# CSI2-WAND_Rev01.net
KiCad netlist of a schematic drawn in Altium Designer
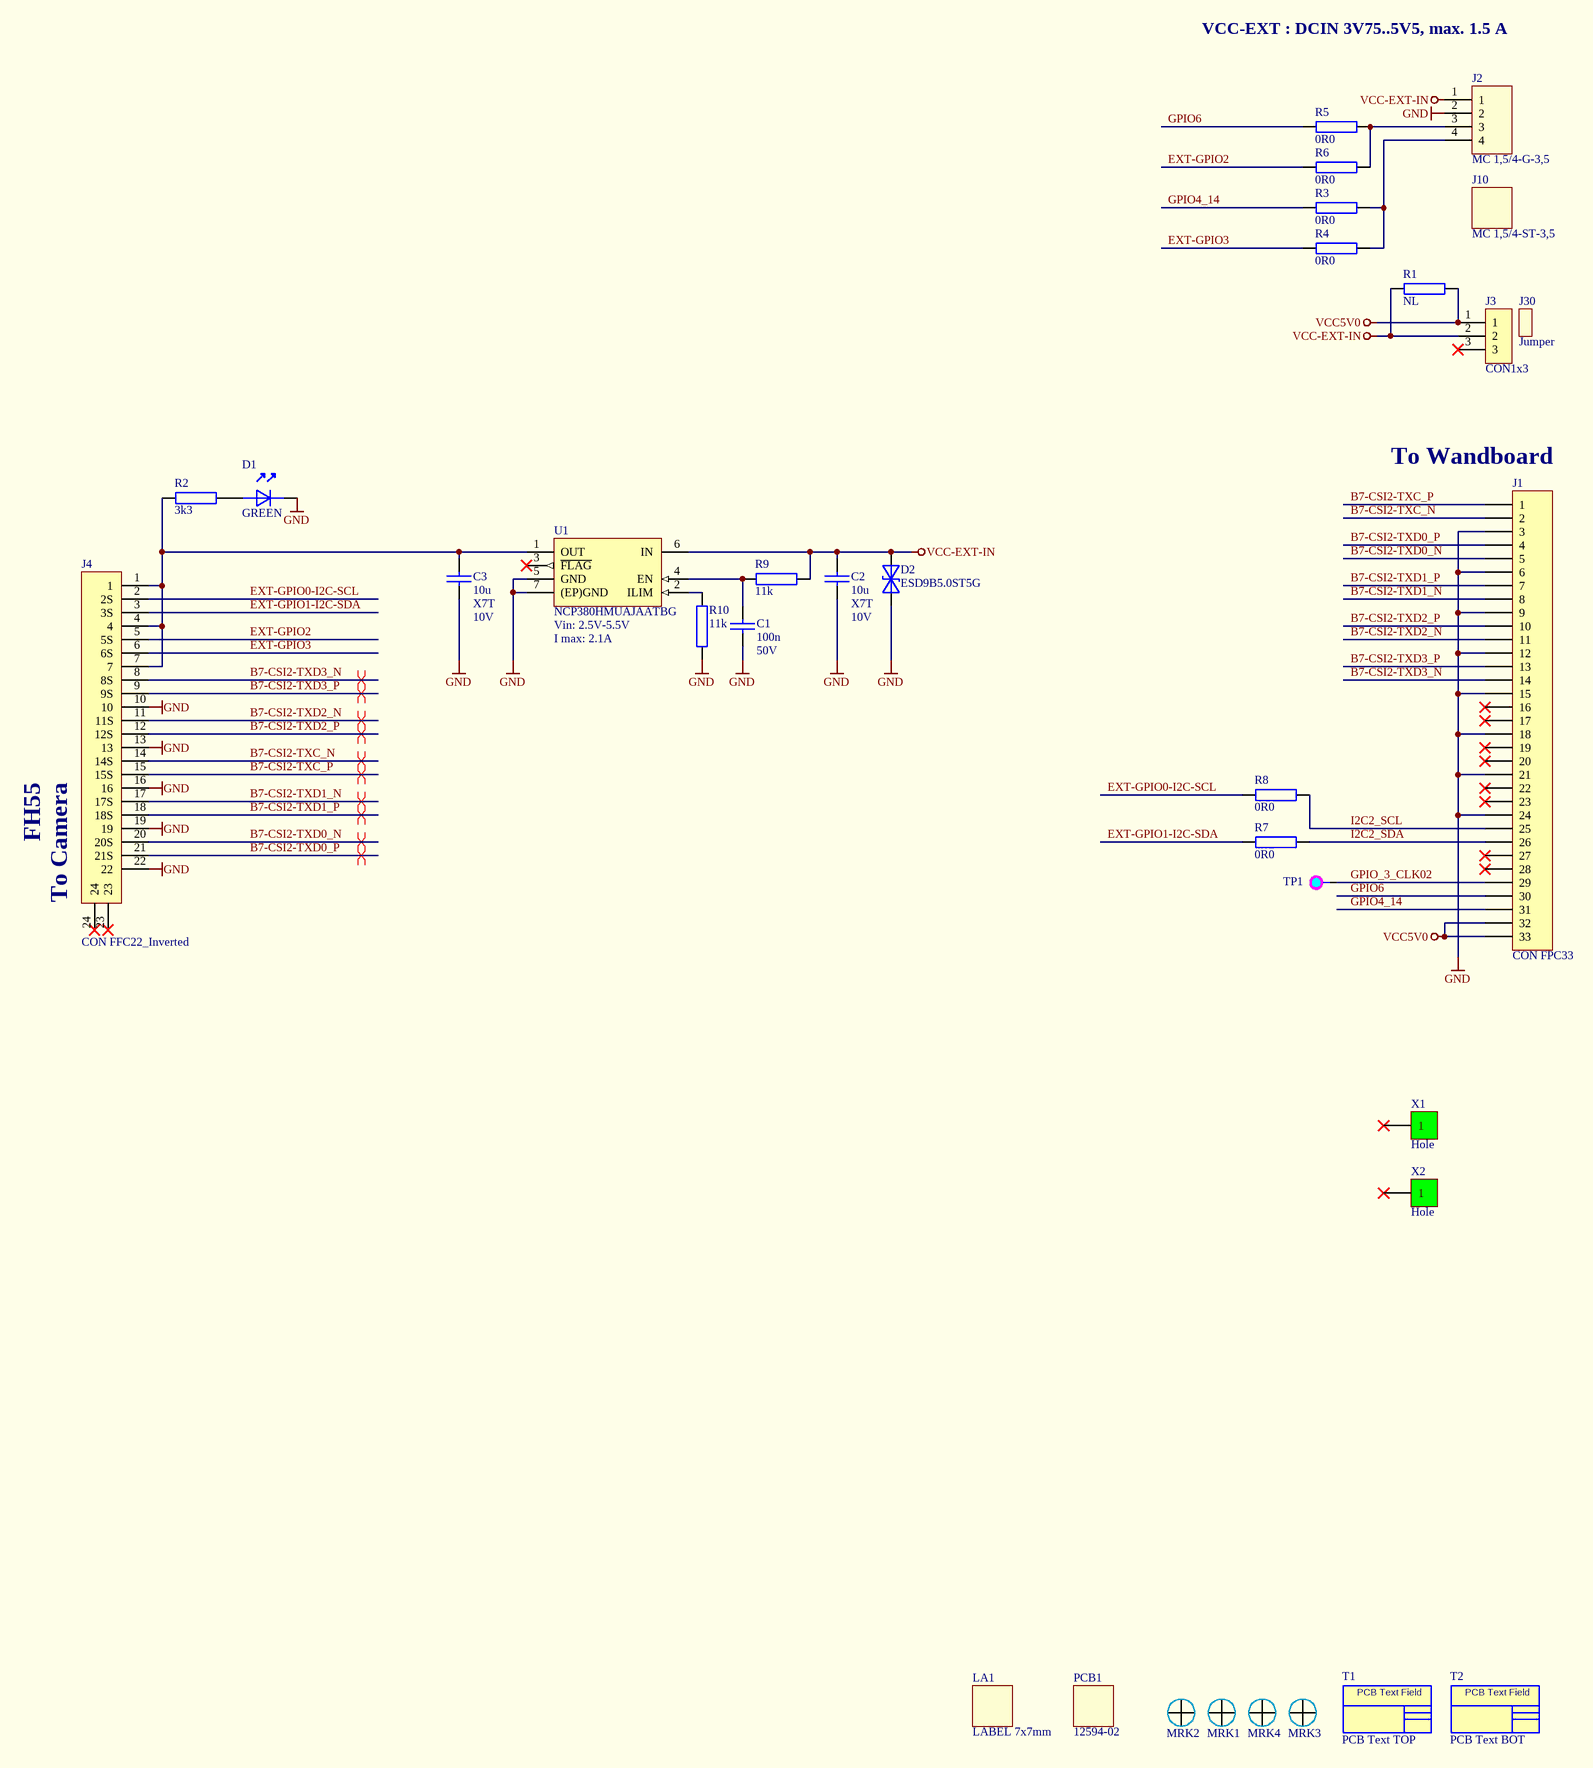
[diagram p0: CSI2-WAND_Rev01.SchDoc]

(export (version "E")
  (design (tool "Eeschema 10.0.6"))
  (components
    (comp (ref "C1")
      (value "100n")
      (footprint "C-0603_1.0")
      (description "Capacitor Ceramic SMD/0603/50V/X7R/10%")
      (fields
        (field (name "KHK PART NUMBER") "K8340023")
        (field (name "MANUFACTURER") "several")
        (field (name "VOLTAGE") "50V")
      )
      (libsource (lib "AVT_KHK_Lib") (part "C 100N 50V X7R 0603"))
    )
    (comp (ref "C2")
      (value "10u")
      (footprint "C-0603_1.0")
      (description "Capacitor Ceramic SMD/0603/10V/X7T/20%/125°C")
      (fields
        (field (name "KHK PART NUMBER") "10509")
        (field (name "MANUFACTURER") "several")
        (field (name "DIELECTRIC") "X7T")
        (field (name "VOLTAGE") "10V")
      )
      (libsource (lib "AVT_KHK_Lib") (part "C 10U 10V X7T 0603 125°C"))
    )
    (comp (ref "C3")
      (value "10u")
      (footprint "C-0603_1.0")
      (description "Capacitor Ceramic SMD/0603/10V/X7T/20%/125°C")
      (fields
        (field (name "KHK PART NUMBER") "10509")
        (field (name "MANUFACTURER") "several")
        (field (name "DIELECTRIC") "X7T")
        (field (name "VOLTAGE") "10V")
      )
      (libsource (lib "AVT_KHK_Lib") (part "C 10U 10V X7T 0603 125°C"))
    )
    (comp (ref "D1")
      (value "GREEN")
      (footprint "D-0603-LED")
      (description "Chip LED green 430mcd")
      (fields (field (name "KHK PART NUMBER") "8172") (field (name "MANUFACTURER") "Würth"))
      (libsource (lib "AVT_KHK_Lib") (part "D LED 0603 green"))
    )
    (comp (ref "D2")
      (value "ESD9B5.0ST5G")
      (footprint "D-SOD923")
      (description "DIODE TVS; 400W; 5.8-7.8V; BIDIRECT")
      (fields (field (name "KHK PART NUMBER") "7250") (field (name "MANUFACTURER") "ON Semiconductor"))
      (libsource (lib "AVT_KHK_Lib") (part "D ESD9B5.0ST5G"))
    )
    (comp (ref "J1")
      (value "CON FPC33")
      (footprint "CON33_FLEX_FPC3.5_5- Inverted Pins")
      (description "FPC Connector 0.5mm FLEX PCB")
      (libsource (lib "AVT_KHK_Lib") (part "CON FPC33_FLEXPCB"))
    )
    (comp (ref "J2")
      (value "MC 1,5/4-G-3,5")
      (footprint "CON_MiniCon 4pol 3mm5")
      (description "Phoenix MC 1,5/4-G-3,5 MiniCon 4polig 3,5mm")
      (fields (field (name "KHK PART NUMBER") "12637") (field (name "MANUFACTURER") "Phoenix"))
      (libsource (lib "AVT_KHK_Lib") (part "CON MiniCon 4pol 3mm5"))
    )
    (comp (ref "J3")
      (value "CON1x3")
      (footprint "CON 1x3 RM2.54")
      (description "Stiftleiste; 1x3; 2.54mm; gerade")
      (fields
        (field (name "MANUFACTURER") "fischer elektronik")
        (field (name "MANUFACTURER PART NUMBER") "SL 11 124 3 G")
      )
      (libsource (lib "AVT_KHK_Lib") (part "CON 1x3 2.54"))
    )
    (comp (ref "J4")
      (value "CON FFC22_Inverted")
      (footprint "J-FH55-22S-0.5SH - Inverted Pins")
      (description "FFC Connector 0.5mm shielded")
      (fields
        (field (name "KHK PART NUMBER") "10357")
        (field (name "MANUFACTURER PART NUMBER") "FH55-22S-0.5SH")
      )
      (libsource (lib "AVT_KHK_Lib") (part "CON FFC22_FH55-22S-0.5SH_Inverted"))
    )
    (comp (ref "J10")
      (value "MC 1,5/4-ST-3,5")
      (description "Phoenix MC 1,5/4-ST-3,5 MiniCon 4polig 3,5mm")
      (fields (field (name "KHK PART NUMBER") "12635") (field (name "MANUFACTURER") "Phoenix"))
      (libsource (lib "AVT_KHK_Lib") (part "CON MiniCon 4pol 3mm5 ST"))
    )
    (comp (ref "J30")
      (value "Jumper")
      (footprint "J-JUMPER-2.54")
      (description "CON/JUMPER/STC02SYAN; 2-pin; 2.54mm; 3A; FEMALE; VERTICAL; BLACK")
      (fields (field (name "KHK PART NUMBER") "13444") (field (name "MANUFACTURER") "several"))
      (libsource (lib "AVT_KHK_Lib") (part "CON Jumper 2.54mm"))
    )
    (comp (ref "LA1")
      (value "LABEL 7x7mm")
      (footprint "PCB LABEL 7x7")
      (fields (field (name "MANUFACTURER") "several"))
      (libsource (lib "AVT_KHK_Lib") (part "PCB LABEL 7x7"))
    )
    (comp (ref "MRK1")
      (value "Marker Single Layer")
      (footprint "PCB_Marker_Pad_top")
      (description "Position Marker for PCBs")
      (libsource (lib "AVT_KHK_Lib") (part "PCB Marker Pad Single Layer"))
    )
    (comp (ref "MRK2")
      (value "Marker Single Layer")
      (footprint "PCB_Marker_Pad_top")
      (description "Position Marker for PCBs")
      (libsource (lib "AVT_KHK_Lib") (part "PCB Marker Pad Single Layer"))
    )
    (comp (ref "MRK3")
      (value "Marker Single Layer")
      (footprint "PCB_Marker_Pad_top")
      (description "Position Marker for PCBs")
      (libsource (lib "AVT_KHK_Lib") (part "PCB Marker Pad Single Layer"))
    )
    (comp (ref "MRK4")
      (value "Marker Single Layer")
      (footprint "PCB_Marker_Pad_top")
      (description "Position Marker for PCBs")
      (libsource (lib "AVT_KHK_Lib") (part "PCB Marker Pad Single Layer"))
    )
    (comp (ref "PCB1")
      (value "12594-02")
      (description "PCB ML04")
      (fields (field (name "MANUFACTURER") "several"))
      (libsource (lib "AVT_KHK_Lib") (part "PCB"))
    )
    (comp (ref "R1")
      (value "NL")
      (footprint "R-0603_0.6")
      (description "Standard Resistor SMD/0603/1%/100mW/TK100")
      (fields (field (name "TOLERANCE") "1%"))
      (libsource (lib "AVT_KHK_Lib") (part "R X 0603"))
    )
    (comp (ref "R2")
      (value "3k3")
      (footprint "R-0603_0.6")
      (description "Standard Resistor SMD/0603/1%/100mW/TK100")
      (fields (field (name "KHK PART NUMBER") "K8250070") (field (name "MANUFACTURER") "several"))
      (libsource (lib "AVT_KHK_Lib") (part "R 3K3 1% 0603"))
    )
    (comp (ref "R3")
      (value "0R0")
      (footprint "R-0603_0.6")
      (description "Standard Resistor SMD/0603/1%/100mW/TK100")
      (fields (field (name "KHK PART NUMBER") "K8250041") (field (name "MANUFACTURER") "several"))
      (libsource (lib "AVT_KHK_Lib") (part "R 0R0 1% 0603"))
    )
    (comp (ref "R4")
      (value "0R0")
      (footprint "R-0603_0.6")
      (description "Standard Resistor SMD/0603/1%/100mW/TK100")
      (fields (field (name "KHK PART NUMBER") "K8250041") (field (name "MANUFACTURER") "several"))
      (libsource (lib "AVT_KHK_Lib") (part "R 0R0 1% 0603"))
    )
    (comp (ref "R5")
      (value "0R0")
      (footprint "R-0603_0.6")
      (description "Standard Resistor SMD/0603/1%/100mW/TK100")
      (fields (field (name "KHK PART NUMBER") "K8250041") (field (name "MANUFACTURER") "several"))
      (libsource (lib "AVT_KHK_Lib") (part "R 0R0 1% 0603"))
    )
    (comp (ref "R6")
      (value "0R0")
      (footprint "R-0603_0.6")
      (description "Standard Resistor SMD/0603/1%/100mW/TK100")
      (fields (field (name "KHK PART NUMBER") "K8250041") (field (name "MANUFACTURER") "several"))
      (libsource (lib "AVT_KHK_Lib") (part "R 0R0 1% 0603"))
    )
    (comp (ref "R7")
      (value "0R0")
      (footprint "R-0603_0.6")
      (description "Standard Resistor SMD/0603/1%/100mW/TK100")
      (fields (field (name "KHK PART NUMBER") "K8250041") (field (name "MANUFACTURER") "several"))
      (libsource (lib "AVT_KHK_Lib") (part "R 0R0 1% 0603"))
    )
    (comp (ref "R8")
      (value "0R0")
      (footprint "R-0603_0.6")
      (description "Standard Resistor SMD/0603/1%/100mW/TK100")
      (fields (field (name "KHK PART NUMBER") "K8250041") (field (name "MANUFACTURER") "several"))
      (libsource (lib "AVT_KHK_Lib") (part "R 0R0 1% 0603"))
    )
    (comp (ref "R9")
      (value "11k")
      (footprint "R-0603_0.6")
      (description "Standard Resistor SMD/0603/1%/100mW/TK100")
      (fields (field (name "KHK PART NUMBER") "K8250147") (field (name "MANUFACTURER") "several"))
      (libsource (lib "AVT_KHK_Lib") (part "R 11K 1% 0603"))
    )
    (comp (ref "R10")
      (value "11k")
      (footprint "R-0603_0.6")
      (description "Standard Resistor SMD/0603/1%/100mW/TK100")
      (fields (field (name "KHK PART NUMBER") "K8250147") (field (name "MANUFACTURER") "several"))
      (libsource (lib "AVT_KHK_Lib") (part "R 11K 1% 0603"))
    )
    (comp (ref "T1")
      (value "PCB Text TOP")
      (footprint "PCB TEXTFIELD TOP 2")
      (description "PCB Textfield TOP")
      (libsource (lib "AVT_KHK_Lib") (part "PCB TEXT FIELD TOP"))
    )
    (comp (ref "T2")
      (value "PCB Text BOT")
      (footprint "PCB TEXTFIELD BOT 2")
      (description "PCB Textfield BOT")
      (libsource (lib "AVT_KHK_Lib") (part "PCB TEXT FIELD BOT"))
    )
    (comp (ref "TP1")
      (value "TP")
      (footprint "TP_11_065")
      (description "Testpoint: Pad=1,1mm; Hole=0,65mm")
      (libsource (lib "AVT_KHK_Lib") (part "TP_11_065"))
    )
    (comp (ref "U1")
      (value "NCP380HMUAJAATBG")
      (footprint "IC-DFN06_2.0x2.0x0.8")
      (description "IC/PWR/LOADSW;1V2-5V5;3A;0R03/WLCSP6/1x1.5x0.63mm")
      (fields
        (field (name "KHK PART NUMBER") "13676")
        (field (name "MANUFACTURER") "onsemi")
        (field (name "VIN") "2.5V-5.5V")
        (field (name "I MAX") "2.1A")
      )
      (libsource (lib "AVT_KHK_Lib") (part "IC  NCP380HMUAJAATBG"))
    )
    (comp (ref "X1")
      (value "Hole")
      (footprint "HOLE-3.2-6.0-DK")
      (description "HOLE M3")
      (libsource (lib "AVT_KHK_Lib") (part "PCB HOLE M3-6-DK"))
    )
    (comp (ref "X2")
      (value "Hole")
      (footprint "HOLE-3.2-6.0-DK")
      (description "HOLE M3")
      (libsource (lib "AVT_KHK_Lib") (part "PCB HOLE M3-6-DK"))
    )
  )
  (nets
    (net (code "1") (name "/B7-CSI2-TXC_N") (class "Default")
      (node (ref "J1") (pin "2") (pinfunction "2_2") (pintype "passive"))
      (node (ref "J4") (pin "14") (pinfunction "14S_14") (pintype "passive"))
    )
    (net (code "2") (name "/B7-CSI2-TXC_P") (class "Default")
      (node (ref "J1") (pin "1") (pinfunction "1_1") (pintype "passive"))
      (node (ref "J4") (pin "15") (pinfunction "15S_15") (pintype "passive"))
    )
    (net (code "3") (name "/B7-CSI2-TXD0_N") (class "Default")
      (node (ref "J1") (pin "5") (pinfunction "5_5") (pintype "passive"))
      (node (ref "J4") (pin "20") (pinfunction "20S_20") (pintype "passive"))
    )
    (net (code "4") (name "/B7-CSI2-TXD0_P") (class "Default")
      (node (ref "J1") (pin "4") (pinfunction "4_4") (pintype "passive"))
      (node (ref "J4") (pin "21") (pinfunction "21S_21") (pintype "passive"))
    )
    (net (code "5") (name "/B7-CSI2-TXD1_N") (class "Default")
      (node (ref "J1") (pin "8") (pinfunction "8_8") (pintype "passive"))
      (node (ref "J4") (pin "17") (pinfunction "17S_17") (pintype "passive"))
    )
    (net (code "6") (name "/B7-CSI2-TXD1_P") (class "Default")
      (node (ref "J1") (pin "7") (pinfunction "7_7") (pintype "passive"))
      (node (ref "J4") (pin "18") (pinfunction "18S_18") (pintype "passive"))
    )
    (net (code "7") (name "/B7-CSI2-TXD2_N") (class "Default")
      (node (ref "J1") (pin "11") (pinfunction "11_11") (pintype "passive"))
      (node (ref "J4") (pin "11") (pinfunction "11S_11") (pintype "passive"))
    )
    (net (code "8") (name "/B7-CSI2-TXD2_P") (class "Default")
      (node (ref "J1") (pin "10") (pinfunction "10_10") (pintype "passive"))
      (node (ref "J4") (pin "12") (pinfunction "12S_12") (pintype "passive"))
    )
    (net (code "9") (name "/B7-CSI2-TXD3_N") (class "Default")
      (node (ref "J1") (pin "14") (pinfunction "14_14") (pintype "passive"))
      (node (ref "J4") (pin "8") (pinfunction "8S_8") (pintype "passive"))
    )
    (net (code "10") (name "/B7-CSI2-TXD3_P") (class "Default")
      (node (ref "J1") (pin "13") (pinfunction "13_13") (pintype "passive"))
      (node (ref "J4") (pin "9") (pinfunction "9S_9") (pintype "passive"))
    )
    (net (code "11") (name "/EXT-GPIO0-I2C-SCL") (class "Default")
      (node (ref "J4") (pin "2") (pinfunction "2S_2") (pintype "passive"))
      (node (ref "R8") (pin "2") (pinfunction "2_2") (pintype "passive"))
    )
    (net (code "12") (name "/EXT-GPIO1-I2C-SDA") (class "Default")
      (node (ref "J4") (pin "3") (pinfunction "3S_3") (pintype "passive"))
      (node (ref "R7") (pin "2") (pinfunction "2_2") (pintype "passive"))
    )
    (net (code "13") (name "/EXT-GPIO2") (class "Default")
      (node (ref "J4") (pin "5") (pinfunction "5S_5") (pintype "passive"))
      (node (ref "R6") (pin "2") (pinfunction "2_2") (pintype "passive"))
    )
    (net (code "14") (name "/EXT-GPIO3") (class "Default")
      (node (ref "J4") (pin "6") (pinfunction "6S_6") (pintype "passive"))
      (node (ref "R4") (pin "2") (pinfunction "2_2") (pintype "passive"))
    )
    (net (code "15") (name "/GPIO4_14") (class "Default")
      (node (ref "J1") (pin "31") (pinfunction "31_31") (pintype "passive"))
      (node (ref "R3") (pin "2") (pinfunction "2_2") (pintype "passive"))
    )
    (net (code "16") (name "/GPIO6") (class "Default")
      (node (ref "J1") (pin "30") (pinfunction "30_30") (pintype "passive"))
      (node (ref "R5") (pin "2") (pinfunction "2_2") (pintype "passive"))
    )
    (net (code "17") (name "/GPIO_3_CLK02") (class "Default")
      (node (ref "J1") (pin "29") (pinfunction "29_29") (pintype "passive"))
      (node (ref "TP1") (pin "1") (pinfunction "1_1") (pintype "passive"))
    )
    (net (code "18") (name "/I2C2_SCL") (class "Default")
      (node (ref "J1") (pin "25") (pinfunction "25_25") (pintype "passive"))
      (node (ref "R8") (pin "1") (pinfunction "1_1") (pintype "passive"))
    )
    (net (code "19") (name "/I2C2_SDA") (class "Default")
      (node (ref "J1") (pin "26") (pinfunction "26_26") (pintype "passive"))
      (node (ref "R7") (pin "1") (pinfunction "1_1") (pintype "passive"))
    )
    (net (code "20") (name "GND") (class "Default")
      (node (ref "C1") (pin "2") (pinfunction "2_2") (pintype "passive"))
      (node (ref "C2") (pin "2") (pinfunction "2_2") (pintype "passive"))
      (node (ref "C3") (pin "2") (pinfunction "2_2") (pintype "passive"))
      (node (ref "D1") (pin "K") (pinfunction "2_K") (pintype "passive"))
      (node (ref "D2") (pin "A") (pinfunction "A_A") (pintype "passive"))
      (node (ref "J1") (pin "12") (pinfunction "12_12") (pintype "passive"))
      (node (ref "J1") (pin "15") (pinfunction "15_15") (pintype "passive"))
      (node (ref "J1") (pin "18") (pinfunction "18_18") (pintype "passive"))
      (node (ref "J1") (pin "21") (pinfunction "21_21") (pintype "passive"))
      (node (ref "J1") (pin "24") (pinfunction "24_24") (pintype "passive"))
      (node (ref "J1") (pin "3") (pinfunction "3_3") (pintype "passive"))
      (node (ref "J1") (pin "6") (pinfunction "6_6") (pintype "passive"))
      (node (ref "J1") (pin "9") (pinfunction "9_9") (pintype "passive"))
      (node (ref "J2") (pin "2") (pinfunction "2_2") (pintype "passive"))
      (node (ref "J4") (pin "10") (pinfunction "10_10") (pintype "passive"))
      (node (ref "J4") (pin "13") (pinfunction "13_13") (pintype "passive"))
      (node (ref "J4") (pin "16") (pinfunction "16_16") (pintype "passive"))
      (node (ref "J4") (pin "19") (pinfunction "19_19") (pintype "passive"))
      (node (ref "J4") (pin "22") (pinfunction "22_22") (pintype "passive"))
      (node (ref "R10") (pin "1") (pinfunction "1_1") (pintype "passive"))
      (node (ref "U1") (pin "5") (pinfunction "GND_5") (pintype "power_in"))
      (node (ref "U1") (pin "7") (pinfunction "(EP)GND_7") (pintype "power_in"))
    )
    (net (code "21") (name "Net-(D1-1)") (class "Default")
      (node (ref "D1") (pin "A") (pinfunction "1_A") (pintype "passive"))
      (node (ref "R2") (pin "2") (pinfunction "2_2") (pintype "passive"))
    )
    (net (code "22") (name "Net-(J2-Pad3)") (class "Default")
      (node (ref "J2") (pin "3") (pinfunction "3_3") (pintype "passive"))
      (node (ref "R5") (pin "1") (pinfunction "1_1") (pintype "passive"))
      (node (ref "R6") (pin "1") (pinfunction "1_1") (pintype "passive"))
    )
    (net (code "23") (name "Net-(J2-Pad4)") (class "Default")
      (node (ref "J2") (pin "4") (pinfunction "4_4") (pintype "passive"))
      (node (ref "R3") (pin "1") (pinfunction "1_1") (pintype "passive"))
      (node (ref "R4") (pin "1") (pinfunction "1_1") (pintype "passive"))
    )
    (net (code "24") (name "Net-(U1-EN)") (class "Default")
      (node (ref "C1") (pin "1") (pinfunction "1_1") (pintype "passive"))
      (node (ref "R9") (pin "2") (pinfunction "2_2") (pintype "passive"))
      (node (ref "U1") (pin "4") (pinfunction "EN_4") (pintype "input"))
    )
    (net (code "25") (name "Net-(U1-ILIM)") (class "Default")
      (node (ref "R10") (pin "2") (pinfunction "2_2") (pintype "passive"))
      (node (ref "U1") (pin "2") (pinfunction "ILIM_2") (pintype "input"))
    )
    (net (code "26") (name "Net-(U1-OUT)") (class "Default")
      (node (ref "C3") (pin "1") (pinfunction "1_1") (pintype "passive"))
      (node (ref "J4") (pin "1") (pinfunction "1_1") (pintype "passive"))
      (node (ref "J4") (pin "4") (pinfunction "4_4") (pintype "passive"))
      (node (ref "J4") (pin "7") (pinfunction "7_7") (pintype "passive"))
      (node (ref "R2") (pin "1") (pinfunction "1_1") (pintype "passive"))
      (node (ref "U1") (pin "1") (pinfunction "OUT_1") (pintype "power_in"))
    )
    (net (code "27") (name "VCC-EXT-IN") (class "Default")
      (node (ref "C2") (pin "1") (pinfunction "1_1") (pintype "passive"))
      (node (ref "D2") (pin "K") (pinfunction "K_K") (pintype "passive"))
      (node (ref "J2") (pin "1") (pinfunction "1_1") (pintype "passive"))
      (node (ref "J3") (pin "2") (pinfunction "2_2") (pintype "passive"))
      (node (ref "R1") (pin "2") (pinfunction "2_2") (pintype "passive"))
      (node (ref "R9") (pin "1") (pinfunction "1_1") (pintype "passive"))
      (node (ref "U1") (pin "6") (pinfunction "IN_6") (pintype "power_in"))
    )
    (net (code "28") (name "VCC5V0") (class "Default")
      (node (ref "J1") (pin "32") (pinfunction "32_32") (pintype "passive"))
      (node (ref "J1") (pin "33") (pinfunction "33_33") (pintype "passive"))
      (node (ref "J3") (pin "1") (pinfunction "1_1") (pintype "passive"))
      (node (ref "R1") (pin "1") (pinfunction "1_1") (pintype "passive"))
    )
    (net (code "29") (name "unconnected-(J1-Pad16)") (class "Default")
      (node (ref "J1") (pin "16") (pinfunction "16_16") (pintype "passive+no_connect"))
    )
    (net (code "30") (name "unconnected-(J1-Pad17)") (class "Default")
      (node (ref "J1") (pin "17") (pinfunction "17_17") (pintype "passive+no_connect"))
    )
    (net (code "31") (name "unconnected-(J1-Pad19)") (class "Default")
      (node (ref "J1") (pin "19") (pinfunction "19_19") (pintype "passive+no_connect"))
    )
    (net (code "32") (name "unconnected-(J1-Pad20)") (class "Default")
      (node (ref "J1") (pin "20") (pinfunction "20_20") (pintype "passive+no_connect"))
    )
    (net (code "33") (name "unconnected-(J1-Pad22)") (class "Default")
      (node (ref "J1") (pin "22") (pinfunction "22_22") (pintype "passive+no_connect"))
    )
    (net (code "34") (name "unconnected-(J1-Pad23)") (class "Default")
      (node (ref "J1") (pin "23") (pinfunction "23_23") (pintype "passive+no_connect"))
    )
    (net (code "35") (name "unconnected-(J1-Pad27)") (class "Default")
      (node (ref "J1") (pin "27") (pinfunction "27_27") (pintype "passive+no_connect"))
    )
    (net (code "36") (name "unconnected-(J1-Pad28)") (class "Default")
      (node (ref "J1") (pin "28") (pinfunction "28_28") (pintype "passive+no_connect"))
    )
    (net (code "37") (name "unconnected-(J3-Pad3)") (class "Default")
      (node (ref "J3") (pin "3") (pinfunction "3_3") (pintype "passive+no_connect"))
    )
    (net (code "38") (name "unconnected-(J4-Pad23)") (class "Default")
      (node (ref "J4") (pin "23") (pinfunction "23_23") (pintype "passive+no_connect"))
    )
    (net (code "39") (name "unconnected-(J4-Pad24)") (class "Default")
      (node (ref "J4") (pin "24") (pinfunction "24_24") (pintype "passive+no_connect"))
    )
    (net (code "40") (name "unconnected-(U1-~{FLAG}-Pad3)") (class "Default")
      (node (ref "U1") (pin "3") (pinfunction "~{FLAG}_3") (pintype "output+no_connect"))
    )
    (net (code "41") (name "unconnected-(X1-Pad1)") (class "Default")
      (node (ref "X1") (pin "1") (pinfunction "1_1") (pintype "passive+no_connect"))
    )
    (net (code "42") (name "unconnected-(X2-Pad1)") (class "Default")
      (node (ref "X2") (pin "1") (pinfunction "1_1") (pintype "passive+no_connect"))
    )
  )
)
